# Mechanical.net
KiCad netlist of a schematic drawn in Altium Designer
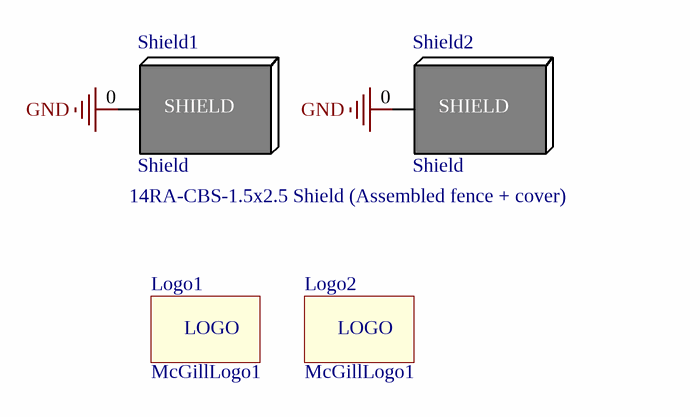
[diagram p0: Mechanical.SchDoc]

(export (version "E")
  (design (tool "Eeschema 10.0.6"))
  (components
    (comp (ref "Logo1")
      (value "McGillLogo1")
      (footprint "McGillLogo1")
      (description "LOGO")
      (libsource (lib "MGMEZZ04") (part "Logo"))
    )
    (comp (ref "Logo2")
      (value "McGillLogo1")
      (footprint "McGillLogo1")
      (description "LOGO")
      (libsource (lib "MGMEZZ04") (part "Logo"))
    )
    (comp (ref "Shield1")
      (value "Shield")
      (footprint "14RA-CBS-1.5x2.5 Shield")
      (description "14RA-CBS-1.5x2.5 Shield (Assembled fence + cover)")
      (fields
        (field (name "PART CONSTRAINTS") "14RA-CBS-1.5x2.5 Shield (Assembled fence + cover)")
        (field (name "MANUFACTURER") "Leadertech")
      )
      (libsource (lib "MGMEZZ04") (part "14RA-CBS-1.5x2.5"))
    )
    (comp (ref "Shield2")
      (value "Shield")
      (footprint "14RA-CBS-1.5x2.5 Shield")
      (description "14RA-CBS-1.5x2.5 Shield (Assembled fence + cover)")
      (fields (field (name "MANUFACTURER") "Leadertech"))
      (libsource (lib "MGMEZZ04") (part "14RA-CBS-1.5x2.5"))
    )
  )
  (nets
    (net (code "1") (name "GND") (class "Default")
      (node (ref "Shield1") (pin "0") (pinfunction "Ground_0") (pintype "passive"))
      (node (ref "Shield2") (pin "0") (pinfunction "Ground_0") (pintype "passive"))
    )
  )
)
